# LV_Power.net
KiCad netlist of a schematic drawn in Altium Designer
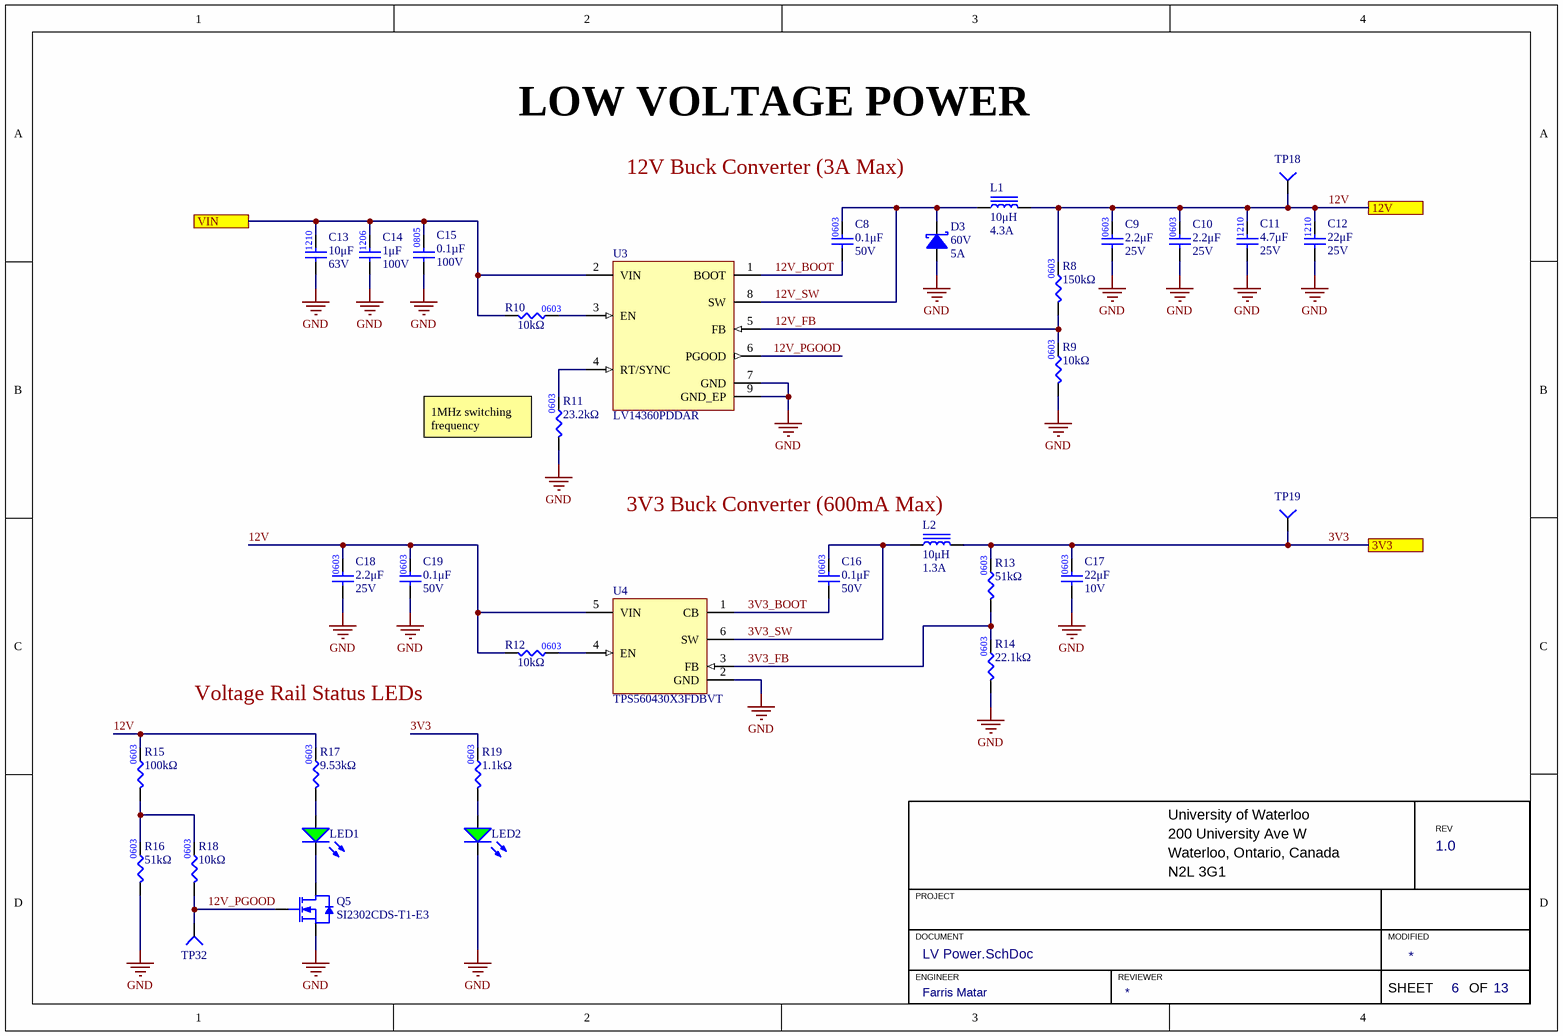
[diagram p0: LV Power.SchDoc]

(export (version "E")
  (design (tool "Eeschema 10.0.6"))
  (components
    (comp (ref "C8")
      (value "0.1μF")
      (footprint "CAP0603")
      (description "CAP CER 0.1UF 50V X7R 0603")
      (fields (field (name "VOLTAGE RATING") "50V") (field (name "Comment") "CAP_0.1uF_50V_0603"))
      (libsource (lib "Personal_Schematic_Library_2022") (part "CAP_0.1uF_50V_0603"))
    )
    (comp (ref "C9")
      (value "2.2μF")
      (footprint "CAP0603")
      (description "CAP CER 2.2UF 25V X5R 0603")
      (fields (field (name "VOLTAGE RATING") "25V") (field (name "Comment") "CAP_2.2uF_25V_0603"))
      (libsource (lib "Personal_Schematic_Library_2022") (part "CAP_2.2uF_25V_0603"))
    )
    (comp (ref "C10")
      (value "2.2μF")
      (footprint "CAP0603")
      (description "CAP CER 2.2UF 25V X5R 0603")
      (fields (field (name "VOLTAGE RATING") "25V") (field (name "Comment") "CAP_2.2uF_25V_0603"))
      (libsource (lib "Personal_Schematic_Library_2022") (part "CAP_2.2uF_25V_0603"))
    )
    (comp (ref "C11")
      (value "4.7μF")
      (footprint "CAP1210")
      (description "CAP CER 4.7UF 25V X8L 1210")
      (fields (field (name "VOLTAGE RATING") "25V") (field (name "Comment") "CAP_4.7uF_25V_1210"))
      (libsource (lib "Personal_Schematic_Library_2022") (part "CAP_4.7uF_25V_1210"))
    )
    (comp (ref "C12")
      (value "22μF")
      (footprint "CAP1210")
      (description "CAP CER 22UF 25V X7R 1210")
      (fields (field (name "VOLTAGE RATING") "25V") (field (name "Comment") "CAP_22uF_25V_1210"))
      (libsource (lib "Personal_Schematic_Library_2022") (part "CAP_22uF_25V_1210"))
    )
    (comp (ref "C13")
      (value "10μF")
      (footprint "CAP1210")
      (description "CAP CER 10UF 63V X7R 1210")
      (fields (field (name "VOLTAGE RATING") "63V") (field (name "Comment") "CAP_10uF_63V_1210"))
      (libsource (lib "Personal_Schematic_Library_2022") (part "CAP_10uF_63V_1210"))
    )
    (comp (ref "C14")
      (value "1μF")
      (footprint "CAP1206")
      (description "CAP CER 1UF 100V X7R 1206")
      (fields (field (name "VOLTAGE RATING") "100V") (field (name "Comment") "CAP_1uF_100V_1206"))
      (libsource (lib "Personal_Schematic_Library_2022") (part "CAP_1uF_100V_1206"))
    )
    (comp (ref "C15")
      (value "0.1µF")
      (footprint "CAP0805")
      (description "CAP CER 0.1UF 100V X7R 0805")
      (fields (field (name "VOLTAGE RATING") "100V") (field (name "Comment") "CAP_0.1uF_100V_0805"))
      (libsource (lib "Personal_Schematic_Library_2022") (part "CAP_0.1uF_100V_0805"))
    )
    (comp (ref "C16")
      (value "0.1μF")
      (footprint "CAP0603")
      (description "CAP CER 0.1UF 50V X7R 0603")
      (fields (field (name "VOLTAGE RATING") "50V") (field (name "Comment") "CAP_0.1uF_50V_0603"))
      (libsource (lib "Personal_Schematic_Library_2022") (part "CAP_0.1uF_50V_0603"))
    )
    (comp (ref "C17")
      (value "22μF")
      (footprint "CAP0603")
      (description "CAP CER 22UF 10V X5R 0603")
      (fields
        (field (name "MANUFACTURER") "Taiyo Yuden")
        (field (name "MANUFACTURER PART NUMBER") "LMK107BBJ226MA-T")
        (field (name "VOLTAGE RATING") "10V")
      )
      (libsource (lib "Personal_Schematic_Library_2022") (part "CAP_22uF_10V_0603"))
    )
    (comp (ref "C18")
      (value "2.2μF")
      (footprint "CAP0603")
      (description "CAP CER 2.2UF 25V X5R 0603")
      (fields (field (name "VOLTAGE RATING") "25V") (field (name "Comment") "CAP_2.2uF_25V_0603"))
      (libsource (lib "Personal_Schematic_Library_2022") (part "CAP_2.2uF_25V_0603"))
    )
    (comp (ref "C19")
      (value "0.1μF")
      (footprint "CAP0603")
      (description "CAP CER 0.1UF 50V X7R 0603")
      (fields (field (name "VOLTAGE RATING") "50V") (field (name "Comment") "CAP_0.1uF_50V_0603"))
      (libsource (lib "Personal_Schematic_Library_2022") (part "CAP_0.1uF_50V_0603"))
    )
    (comp (ref "D3")
      (value "DIO_SCHOTTKY_60V_5A")
      (footprint "DIO-INC_SMA")
      (description "DIODE SCHOTTKY 60V 5A SMA")
      (fields (field (name "VR (MAX)") "60V") (field (name "CURRENT - AVERAGE RECTIFIED (IO)") "5A"))
      (libsource (lib "Personal_Schematic_Library_2022") (part "DIO_SCHOTTKY_60V_5A"))
    )
    (comp (ref "L1")
      (value "10μH")
      (footprint "IND_MURATA_DS106C2")
      (description "FIXED IND 10UH 4.3A 28 MOHM SMD")
      (fields (field (name "CURRENT RATING") "4.3A") (field (name "Comment") "IND_10uH_4.3A"))
      (libsource (lib "Personal_Schematic_Library_2022") (part "IND_10uH_4.3A"))
    )
    (comp (ref "L2")
      (value "10μH")
      (footprint "IND_ABRACON_ASPI4030S")
      (description "FIXED IND 12UH 1.3A 135 MOHM SMD")
      (fields (field (name "CURRENT RATING") "1.3A") (field (name "Comment") "IND_10uH_1.3A"))
      (libsource (lib "Personal_Schematic_Library_2022") (part "IND_10uH_1.3A"))
    )
    (comp (ref "LED1")
      (value "LED_GREEN_0805")
      (footprint "LED_0805_GREEN")
      (description "LED GREEN DIFFUSED 0805 SMD")
      (libsource (lib "Personal_Schematic_Library_2022") (part "LED_GREEN_0805"))
    )
    (comp (ref "LED2")
      (value "LED_GREEN_0805")
      (footprint "LED_0805_GREEN")
      (description "LED GREEN DIFFUSED 0805 SMD")
      (libsource (lib "Personal_Schematic_Library_2022") (part "LED_GREEN_0805"))
    )
    (comp (ref "Q5")
      (value "NMOS_20V_6A")
      (footprint "SOT23-3")
      (description "MOSFET N-CH 20V 2.6A SOT23-3")
      (fields (field (name "MANUFACTURER PART NUMBER 1") "SI2302CDS-T1-E3"))
      (libsource (lib "Personal_Schematic_Library_2022") (part "NMOS_20V_2.6A"))
    )
    (comp (ref "R8")
      (value "150kΩ")
      (footprint "RES0603")
      (description "RES 150K OHM 1% 1/10W 0603")
      (fields (field (name "Comment") "RES_150kΩ_0603_1%"))
      (libsource (lib "Personal_Schematic_Library_2022") (part "RES_150kΩ_0603_1%"))
    )
    (comp (ref "R9")
      (value "10kΩ")
      (footprint "RES0603")
      (description "RES 10K OHM 1% 1/8W 0603")
      (fields (field (name "Comment") "RES_10kΩ_0603_1%"))
      (libsource (lib "Personal_Schematic_Library_2022") (part "RES_10kΩ_0603_1%"))
    )
    (comp (ref "R10")
      (value "10kΩ")
      (footprint "RES0603")
      (description "RES 10K OHM 1% 1/8W 0603")
      (fields (field (name "Comment") "RES_10kΩ_0603_1%"))
      (libsource (lib "Personal_Schematic_Library_2022") (part "RES_10kΩ_0603_1%"))
    )
    (comp (ref "R11")
      (value "23.2kΩ")
      (footprint "RES0603")
      (description "RES 23.2K OHM 1% 1/10W 0603")
      (fields (field (name "Comment") "RES_23.2kΩ_0603_1%"))
      (libsource (lib "Personal_Schematic_Library_2022") (part "RES_23.2kΩ_0603_1%"))
    )
    (comp (ref "R12")
      (value "10kΩ")
      (footprint "RES0603")
      (description "RES 10K OHM 1% 1/8W 0603")
      (fields (field (name "Comment") "RES_10kΩ_0603_1%"))
      (libsource (lib "Personal_Schematic_Library_2022") (part "RES_10kΩ_0603_1%"))
    )
    (comp (ref "R13")
      (value "51kΩ")
      (footprint "RES0603")
      (description "RES 51K OHM 1% 1/10W 0603")
      (fields (field (name "Comment") "RES_51kΩ_0603_1%"))
      (libsource (lib "Personal_Schematic_Library_2022") (part "RES_51kΩ_0603_1%"))
    )
    (comp (ref "R14")
      (value "22.1kΩ")
      (footprint "RES0603")
      (description "RES 22.1K OHM 1% 1/10W 0603")
      (fields (field (name "Comment") "RES_22.1kΩ_0603_1%"))
      (libsource (lib "Personal_Schematic_Library_2022") (part "RES_22.1kΩ_0603_1%"))
    )
    (comp (ref "R15")
      (value "100kΩ")
      (footprint "RES0603")
      (description "RES 100K OHM 1% 1/10W 0603")
      (fields (field (name "Comment") "RES_100kΩ_0603_1%"))
      (libsource (lib "Personal_Schematic_Library_2022") (part "RES_100kΩ_0603_1%"))
    )
    (comp (ref "R16")
      (value "51kΩ")
      (footprint "RES0603")
      (description "RES 51K OHM 1% 1/10W 0603")
      (fields (field (name "Comment") "RES_51kΩ_0603_1%"))
      (libsource (lib "Personal_Schematic_Library_2022") (part "RES_51kΩ_0603_1%"))
    )
    (comp (ref "R17")
      (value "9.53kΩ")
      (footprint "RES0603")
      (description "RES 9.53K OHM 1% 1/10W 0603")
      (fields (field (name "Comment") "RES_9.53kΩ_0603_1%"))
      (libsource (lib "Personal_Schematic_Library_2022") (part "RES_9.53kΩ_0603_1%"))
    )
    (comp (ref "R18")
      (value "10kΩ")
      (footprint "RES0603")
      (description "RES 10K OHM 1% 1/8W 0603")
      (fields (field (name "Comment") "RES_10kΩ_0603_1%"))
      (libsource (lib "Personal_Schematic_Library_2022") (part "RES_10kΩ_0603_1%"))
    )
    (comp (ref "R19")
      (value "1.1kΩ")
      (footprint "RES0603")
      (description "RES 1.1K OHM 1% 1/10W 0603")
      (fields (field (name "Comment") "RES_1.1kΩ_0603_1%"))
      (libsource (lib "Personal_Schematic_Library_2022") (part "RES_1.1kΩ_0603_1%"))
    )
    (comp (ref "TP18")
      (value "TESTPOINT_KEYSTONE_LOOP")
      (footprint "KEYSTONE_5019")
      (description "PC TEST POINT MINIATURE")
      (libsource (lib "Personal_Schematic_Library_2022") (part "TESTPOINT_KEYSTONE_LOOP"))
    )
    (comp (ref "TP19")
      (value "TESTPOINT_KEYSTONE_LOOP")
      (footprint "KEYSTONE_5019")
      (description "PC TEST POINT MINIATURE")
      (libsource (lib "Personal_Schematic_Library_2022") (part "TESTPOINT_KEYSTONE_LOOP"))
    )
    (comp (ref "TP32")
      (value "TESTPOINT_1MM_CIRCLE")
      (footprint "TESTPOINT_CIRCLE_1MM")
      (description "TESTPOINT 1MM CIRCLE")
      (libsource (lib "Personal_Schematic_Library_2022") (part "TESTPOINT_1MM_CIRCLE"))
    )
    (comp (ref "U3")
      (value "LV14360PDDAR")
      (footprint "TI_8-PowerPad-SOIC")
      (description "IC REG BUCK ADJ 3A 8SOPWR")
      (libsource (lib "Personal_Schematic_Library_2022") (part "LV14360PDDAR"))
    )
    (comp (ref "U4")
      (value "TPS560430X3FDBVT")
      (footprint "SOT23-6")
      (description "IC REG BUCK 3.3V 600MA SOT23-6")
      (libsource (lib "Personal_Schematic_Library_2022") (part "TPS560430X3FDBVT"))
    )
  )
  (nets
    (net (code "1") (name "/3V3") (class "Default")
      (node (ref "C17") (pin "2") (pinfunction "2_2") (pintype "passive"))
      (node (ref "L2") (pin "2") (pinfunction "2_2") (pintype "passive"))
      (node (ref "R13") (pin "2") (pinfunction "2_2") (pintype "passive"))
      (node (ref "R19") (pin "2") (pinfunction "2_2") (pintype "passive"))
      (node (ref "TP19") (pin "1") (pinfunction "=value_1") (pintype "passive"))
    )
    (net (code "2") (name "/3V3_BOOT") (class "Default")
      (node (ref "C16") (pin "1") (pinfunction "1_1") (pintype "passive"))
      (node (ref "U4") (pin "1") (pinfunction "CB_1") (pintype "power_in"))
    )
    (net (code "3") (name "/3V3_FB") (class "Default")
      (node (ref "R13") (pin "1") (pinfunction "1_1") (pintype "passive"))
      (node (ref "R14") (pin "2") (pinfunction "2_2") (pintype "passive"))
      (node (ref "U4") (pin "3") (pinfunction "FB_3") (pintype "input"))
    )
    (net (code "4") (name "/3V3_SW") (class "Default")
      (node (ref "C16") (pin "2") (pinfunction "2_2") (pintype "passive"))
      (node (ref "L2") (pin "1") (pinfunction "1_1") (pintype "passive"))
      (node (ref "U4") (pin "6") (pinfunction "SW_6") (pintype "power_in"))
    )
    (net (code "5") (name "/12V") (class "Default")
      (node (ref "C10") (pin "2") (pinfunction "2_2") (pintype "passive"))
      (node (ref "C11") (pin "2") (pinfunction "2_2") (pintype "passive"))
      (node (ref "C12") (pin "2") (pinfunction "2_2") (pintype "passive"))
      (node (ref "C18") (pin "2") (pinfunction "2_2") (pintype "passive"))
      (node (ref "C19") (pin "2") (pinfunction "2_2") (pintype "passive"))
      (node (ref "C9") (pin "2") (pinfunction "2_2") (pintype "passive"))
      (node (ref "L1") (pin "2") (pinfunction "2_2") (pintype "passive"))
      (node (ref "R12") (pin "1") (pinfunction "1_1") (pintype "passive"))
      (node (ref "R15") (pin "2") (pinfunction "2_2") (pintype "passive"))
      (node (ref "R17") (pin "2") (pinfunction "2_2") (pintype "passive"))
      (node (ref "R8") (pin "2") (pinfunction "2_2") (pintype "passive"))
      (node (ref "TP18") (pin "1") (pinfunction "=value_1") (pintype "passive"))
      (node (ref "U4") (pin "5") (pinfunction "VIN_5") (pintype "power_in"))
    )
    (net (code "6") (name "/12V_BOOT") (class "Default")
      (node (ref "C8") (pin "1") (pinfunction "1_1") (pintype "passive"))
      (node (ref "U3") (pin "1") (pinfunction "BOOT_1") (pintype "power_in"))
    )
    (net (code "7") (name "/12V_FB") (class "Default")
      (node (ref "R8") (pin "1") (pinfunction "1_1") (pintype "passive"))
      (node (ref "R9") (pin "2") (pinfunction "2_2") (pintype "passive"))
      (node (ref "U3") (pin "5") (pinfunction "FB_5") (pintype "input"))
    )
    (net (code "8") (name "/12V_PGOOD") (class "Default")
      (node (ref "Q5") (pin "1") (pinfunction "GATE_1") (pintype "passive"))
      (node (ref "R18") (pin "1") (pinfunction "1_1") (pintype "passive"))
      (node (ref "TP32") (pin "1") (pinfunction "=value_1") (pintype "passive"))
      (node (ref "U3") (pin "6") (pinfunction "PGOOD_6") (pintype "output"))
    )
    (net (code "9") (name "/12V_SW") (class "Default")
      (node (ref "C8") (pin "2") (pinfunction "2_2") (pintype "passive"))
      (node (ref "D3") (pin "1") (pinfunction "Cathode_1") (pintype "passive"))
      (node (ref "L1") (pin "1") (pinfunction "1_1") (pintype "passive"))
      (node (ref "U3") (pin "8") (pinfunction "SW_8") (pintype "power_in"))
    )
    (net (code "10") (name "/VIN") (class "Default")
      (node (ref "C13") (pin "2") (pinfunction "2_2") (pintype "passive"))
      (node (ref "C14") (pin "2") (pinfunction "2_2") (pintype "passive"))
      (node (ref "C15") (pin "2") (pinfunction "2_2") (pintype "passive"))
      (node (ref "R10") (pin "1") (pinfunction "1_1") (pintype "passive"))
      (node (ref "U3") (pin "2") (pinfunction "VIN_2") (pintype "power_in"))
    )
    (net (code "11") (name "GND") (class "Default")
      (node (ref "C10") (pin "1") (pinfunction "1_1") (pintype "passive"))
      (node (ref "C11") (pin "1") (pinfunction "1_1") (pintype "passive"))
      (node (ref "C12") (pin "1") (pinfunction "1_1") (pintype "passive"))
      (node (ref "C13") (pin "1") (pinfunction "1_1") (pintype "passive"))
      (node (ref "C14") (pin "1") (pinfunction "1_1") (pintype "passive"))
      (node (ref "C15") (pin "1") (pinfunction "1_1") (pintype "passive"))
      (node (ref "C17") (pin "1") (pinfunction "1_1") (pintype "passive"))
      (node (ref "C18") (pin "1") (pinfunction "1_1") (pintype "passive"))
      (node (ref "C19") (pin "1") (pinfunction "1_1") (pintype "passive"))
      (node (ref "C9") (pin "1") (pinfunction "1_1") (pintype "passive"))
      (node (ref "D3") (pin "2") (pinfunction "Anode_2") (pintype "passive"))
      (node (ref "LED2") (pin "2") (pinfunction "K_2") (pintype "passive"))
      (node (ref "Q5") (pin "2") (pinfunction "SOURCE_2") (pintype "passive"))
      (node (ref "R11") (pin "1") (pinfunction "1_1") (pintype "passive"))
      (node (ref "R14") (pin "1") (pinfunction "1_1") (pintype "passive"))
      (node (ref "R16") (pin "1") (pinfunction "1_1") (pintype "passive"))
      (node (ref "R9") (pin "1") (pinfunction "1_1") (pintype "passive"))
      (node (ref "U3") (pin "7") (pinfunction "GND_7") (pintype "power_in"))
      (node (ref "U3") (pin "9") (pinfunction "GND_EP_9") (pintype "power_in"))
      (node (ref "U4") (pin "2") (pinfunction "GND_2") (pintype "power_in"))
    )
    (net (code "12") (name "Net-(LED1-A)") (class "Default")
      (node (ref "LED1") (pin "1") (pinfunction "A_1") (pintype "passive"))
      (node (ref "R17") (pin "1") (pinfunction "1_1") (pintype "passive"))
    )
    (net (code "13") (name "Net-(LED1-K)") (class "Default")
      (node (ref "LED1") (pin "2") (pinfunction "K_2") (pintype "passive"))
      (node (ref "Q5") (pin "3") (pinfunction "DRAIN_3") (pintype "passive"))
    )
    (net (code "14") (name "Net-(LED2-A)") (class "Default")
      (node (ref "LED2") (pin "1") (pinfunction "A_1") (pintype "passive"))
      (node (ref "R19") (pin "1") (pinfunction "1_1") (pintype "passive"))
    )
    (net (code "15") (name "Net-(R15-Pad1)") (class "Default")
      (node (ref "R15") (pin "1") (pinfunction "1_1") (pintype "passive"))
      (node (ref "R16") (pin "2") (pinfunction "2_2") (pintype "passive"))
      (node (ref "R18") (pin "2") (pinfunction "2_2") (pintype "passive"))
    )
    (net (code "16") (name "Net-(U3-EN)") (class "Default")
      (node (ref "R10") (pin "2") (pinfunction "2_2") (pintype "passive"))
      (node (ref "U3") (pin "3") (pinfunction "EN_3") (pintype "input"))
    )
    (net (code "17") (name "Net-(U3-RT{slash}SYNC)") (class "Default")
      (node (ref "R11") (pin "2") (pinfunction "2_2") (pintype "passive"))
      (node (ref "U3") (pin "4") (pinfunction "RT/SYNC_4") (pintype "input"))
    )
    (net (code "18") (name "Net-(U4-EN)") (class "Default")
      (node (ref "R12") (pin "2") (pinfunction "2_2") (pintype "passive"))
      (node (ref "U4") (pin "4") (pinfunction "EN_4") (pintype "input"))
    )
  )
)
